# LCDTFT_CTRL_FT812.net
KiCad netlist of a schematic drawn in Altium Designer
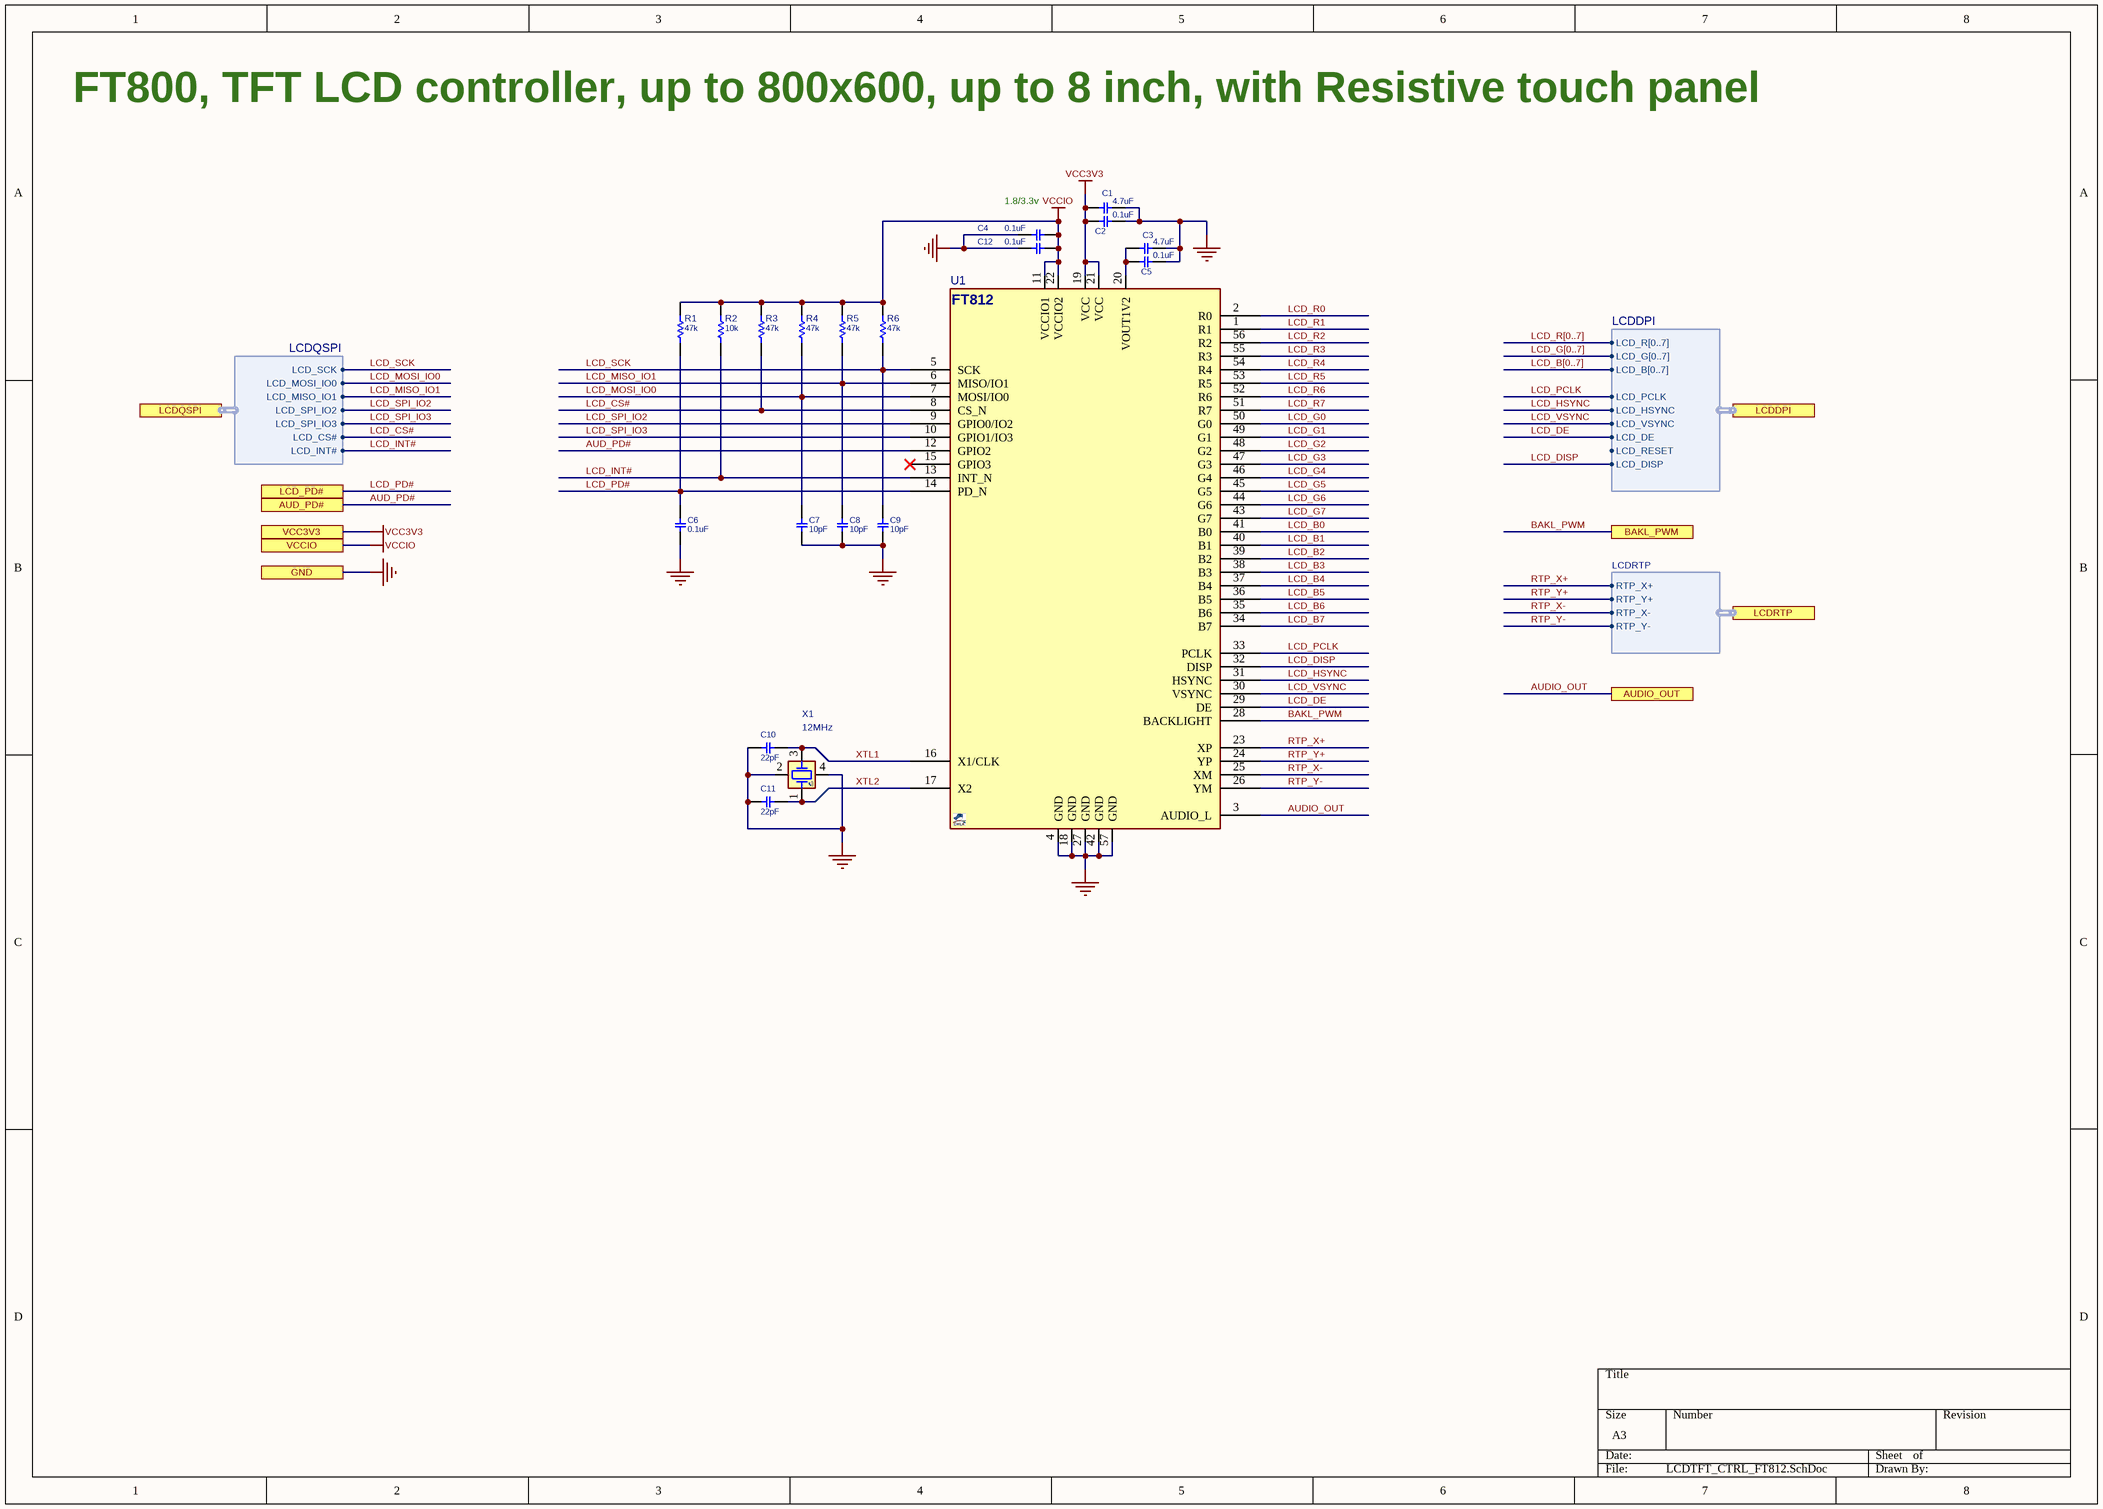
[diagram p0: LCDTFT_CTRL_FT812.SchDoc]

(export (version "E")
  (design (tool "Eeschema 10.0.6"))
  (components
    (comp (ref "C1")
      (value "4.7uF")
      (footprint "C0603")
      (description "CAP, MLCC")
      (libsource (lib "passive_smd") (part "CAP_SMD_MLCC"))
    )
    (comp (ref "C2")
      (value "0.1uF")
      (footprint "C0402")
      (description "CAP, MLCC")
      (fields (field (name "MANF_P#") "GRM155R71H104KE14D") (field (name "MANF") "Murata"))
      (libsource (lib "passive_smd") (part "CAP_SMD_MLCC"))
    )
    (comp (ref "C3")
      (value "4.7uF")
      (footprint "C0603")
      (description "CAP, MLCC")
      (libsource (lib "passive_smd") (part "CAP_SMD_MLCC"))
    )
    (comp (ref "C4")
      (value "0.1uF")
      (footprint "C0402")
      (description "CAP, MLCC")
      (fields (field (name "MANF_P#") "GRM155R71H104KE14D") (field (name "MANF") "Murata"))
      (libsource (lib "passive_smd") (part "CAP_SMD_MLCC"))
    )
    (comp (ref "C5")
      (value "0.1uF")
      (footprint "C0402")
      (description "CAP, MLCC")
      (fields (field (name "MANF_P#") "GRM155R71H104KE14D") (field (name "MANF") "Murata"))
      (libsource (lib "passive_smd") (part "CAP_SMD_MLCC"))
    )
    (comp (ref "C6")
      (value "0.1uF")
      (footprint "C0402")
      (description "CAP, MLCC")
      (fields (field (name "MANF_P#") "GRM155R71H104KE14D") (field (name "MANF") "Murata"))
      (libsource (lib "passive_smd") (part "CAP_SMD_MLCC"))
    )
    (comp (ref "C7")
      (value "10pF")
      (footprint "C0402")
      (description "CAP, MLCC")
      (libsource (lib "passive_smd") (part "CAP_SMD_MLCC"))
    )
    (comp (ref "C8")
      (value "10pF")
      (footprint "C0402")
      (description "CAP, MLCC")
      (libsource (lib "passive_smd") (part "CAP_SMD_MLCC"))
    )
    (comp (ref "C9")
      (value "10pF")
      (footprint "C0402")
      (description "CAP, MLCC")
      (libsource (lib "passive_smd") (part "CAP_SMD_MLCC"))
    )
    (comp (ref "C10")
      (value "22pF")
      (footprint "C0402")
      (description "CAP, MLCC")
      (libsource (lib "passive_smd") (part "CAP_SMD_MLCC"))
    )
    (comp (ref "C11")
      (value "22pF")
      (footprint "C0402")
      (description "CAP, MLCC")
      (libsource (lib "passive_smd") (part "CAP_SMD_MLCC"))
    )
    (comp (ref "C12")
      (value "0.1uF")
      (footprint "C0402")
      (description "CAP, MLCC")
      (fields (field (name "MANF_P#") "GRM155R71H104KE14D") (field (name "MANF") "Murata"))
      (libsource (lib "passive_smd") (part "CAP_SMD_MLCC"))
    )
    (comp (ref "R1")
      (value "47k")
      (footprint "R0402")
      (description "RESISTOR, SMD")
      (libsource (lib "passive_res_smd") (part "RES_SMD"))
    )
    (comp (ref "R2")
      (value "10k")
      (footprint "R0402")
      (description "RESISTOR, SMD")
      (libsource (lib "passive_res_smd") (part "RES_SMD"))
    )
    (comp (ref "R3")
      (value "47k")
      (footprint "R0402")
      (description "RESISTOR, SMD")
      (libsource (lib "passive_res_smd") (part "RES_SMD"))
    )
    (comp (ref "R4")
      (value "47k")
      (footprint "R0402")
      (description "RESISTOR, SMD")
      (libsource (lib "passive_res_smd") (part "RES_SMD"))
    )
    (comp (ref "R5")
      (value "47k")
      (footprint "R0402")
      (description "RESISTOR, SMD")
      (libsource (lib "passive_res_smd") (part "RES_SMD"))
    )
    (comp (ref "R6")
      (value "47k")
      (footprint "R0402")
      (description "RESISTOR, SMD")
      (libsource (lib "passive_res_smd") (part "RES_SMD"))
    )
    (comp (ref "U1")
      (value "FT812")
      (footprint "QFN50_56T")
      (description "LCD Display Controller, Embedded Video Engine, QFN-56")
      (fields (field (name "MANF") "FTDI/Bridgetek") (field (name "MANF_P#") "FT812Q"))
      (libsource (lib "lcdtft_controller") (part "FT812_QFN56"))
    )
    (comp (ref "X1")
      (value "12MHz")
      (footprint "XTL_4_3225")
      (description "Crystal 12MHz")
      (fields (field (name "MANF") "ECS") (field (name "MANF_P#") "ECS-120-18-33-JEM-TR"))
      (libsource (lib "crystal") (part "XTL_4_12MHz_3225"))
    )
  )
  (nets
    (net (code "4") (name "/AUDIO_OUT") (class "Default")
      (node (ref "U1") (pin "3") (pinfunction "AUDIO_L_3") (pintype "passive"))
    )
    (net (code "5") (name "/AUD_PD#") (class "Default")
      (node (ref "U1") (pin "12") (pinfunction "GPIO2_12") (pintype "passive"))
    )
    (net (code "6") (name "/BAKL_PWM") (class "Default")
      (node (ref "U1") (pin "28") (pinfunction "BACKLIGHT_28") (pintype "passive"))
    )
    (net (code "8") (name "/LCD_B0") (class "Default")
      (node (ref "U1") (pin "41") (pinfunction "B0_41") (pintype "passive"))
    )
    (net (code "9") (name "/LCD_B1") (class "Default")
      (node (ref "U1") (pin "40") (pinfunction "B1_40") (pintype "passive"))
    )
    (net (code "10") (name "/LCD_B2") (class "Default")
      (node (ref "U1") (pin "39") (pinfunction "B2_39") (pintype "passive"))
    )
    (net (code "11") (name "/LCD_B3") (class "Default")
      (node (ref "U1") (pin "38") (pinfunction "B3_38") (pintype "passive"))
    )
    (net (code "12") (name "/LCD_B4") (class "Default")
      (node (ref "U1") (pin "37") (pinfunction "B4_37") (pintype "passive"))
    )
    (net (code "13") (name "/LCD_B5") (class "Default")
      (node (ref "U1") (pin "36") (pinfunction "B5_36") (pintype "passive"))
    )
    (net (code "14") (name "/LCD_B6") (class "Default")
      (node (ref "U1") (pin "35") (pinfunction "B6_35") (pintype "passive"))
    )
    (net (code "15") (name "/LCD_B7") (class "Default")
      (node (ref "U1") (pin "34") (pinfunction "B7_34") (pintype "passive"))
    )
    (net (code "16") (name "/LCD_CS#") (class "Default")
      (node (ref "R3") (pin "2") (pinfunction "2_2") (pintype "passive"))
      (node (ref "U1") (pin "8") (pinfunction "CS_N_8") (pintype "passive"))
    )
    (net (code "17") (name "/LCD_DE") (class "Default")
      (node (ref "U1") (pin "29") (pinfunction "DE_29") (pintype "passive"))
    )
    (net (code "18") (name "/LCD_DISP") (class "Default")
      (node (ref "U1") (pin "32") (pinfunction "DISP_32") (pintype "passive"))
    )
    (net (code "19") (name "/LCD_G0") (class "Default")
      (node (ref "U1") (pin "50") (pinfunction "G0_50") (pintype "passive"))
    )
    (net (code "20") (name "/LCD_G1") (class "Default")
      (node (ref "U1") (pin "49") (pinfunction "G1_49") (pintype "passive"))
    )
    (net (code "21") (name "/LCD_G2") (class "Default")
      (node (ref "U1") (pin "48") (pinfunction "G2_48") (pintype "passive"))
    )
    (net (code "22") (name "/LCD_G3") (class "Default")
      (node (ref "U1") (pin "47") (pinfunction "G3_47") (pintype "passive"))
    )
    (net (code "23") (name "/LCD_G4") (class "Default")
      (node (ref "U1") (pin "46") (pinfunction "G4_46") (pintype "passive"))
    )
    (net (code "24") (name "/LCD_G5") (class "Default")
      (node (ref "U1") (pin "45") (pinfunction "G5_45") (pintype "passive"))
    )
    (net (code "25") (name "/LCD_G6") (class "Default")
      (node (ref "U1") (pin "44") (pinfunction "G6_44") (pintype "passive"))
    )
    (net (code "26") (name "/LCD_G7") (class "Default")
      (node (ref "U1") (pin "43") (pinfunction "G7_43") (pintype "passive"))
    )
    (net (code "28") (name "/LCD_HSYNC") (class "Default")
      (node (ref "U1") (pin "31") (pinfunction "HSYNC_31") (pintype "passive"))
    )
    (net (code "29") (name "/LCD_INT#") (class "Default")
      (node (ref "R2") (pin "2") (pinfunction "2_2") (pintype "passive"))
      (node (ref "U1") (pin "13") (pinfunction "INT_N_13") (pintype "passive"))
    )
    (net (code "30") (name "/LCD_MISO_IO1") (class "Default")
      (node (ref "C8") (pin "1") (pinfunction "1_1") (pintype "passive"))
      (node (ref "R5") (pin "2") (pinfunction "2_2") (pintype "passive"))
      (node (ref "U1") (pin "6") (pinfunction "MISO/IO1_6") (pintype "passive"))
    )
    (net (code "31") (name "/LCD_MOSI_IO0") (class "Default")
      (node (ref "C7") (pin "1") (pinfunction "1_1") (pintype "passive"))
      (node (ref "R4") (pin "2") (pinfunction "2_2") (pintype "passive"))
      (node (ref "U1") (pin "7") (pinfunction "MOSI/IO0_7") (pintype "passive"))
    )
    (net (code "32") (name "/LCD_PCLK") (class "Default")
      (node (ref "U1") (pin "33") (pinfunction "PCLK_33") (pintype "passive"))
    )
    (net (code "33") (name "/LCD_PD#") (class "Default")
      (node (ref "C6") (pin "1") (pinfunction "1_1") (pintype "passive"))
      (node (ref "R1") (pin "2") (pinfunction "2_2") (pintype "passive"))
      (node (ref "U1") (pin "14") (pinfunction "PD_N_14") (pintype "passive"))
    )
    (net (code "34") (name "/LCD_R0") (class "Default")
      (node (ref "U1") (pin "2") (pinfunction "R0_2") (pintype "passive"))
    )
    (net (code "35") (name "/LCD_R1") (class "Default")
      (node (ref "U1") (pin "1") (pinfunction "R1_1") (pintype "passive"))
    )
    (net (code "36") (name "/LCD_R2") (class "Default")
      (node (ref "U1") (pin "56") (pinfunction "R2_56") (pintype "passive"))
    )
    (net (code "37") (name "/LCD_R3") (class "Default")
      (node (ref "U1") (pin "55") (pinfunction "R3_55") (pintype "passive"))
    )
    (net (code "38") (name "/LCD_R4") (class "Default")
      (node (ref "U1") (pin "54") (pinfunction "R4_54") (pintype "passive"))
    )
    (net (code "39") (name "/LCD_R5") (class "Default")
      (node (ref "U1") (pin "53") (pinfunction "R5_53") (pintype "passive"))
    )
    (net (code "40") (name "/LCD_R6") (class "Default")
      (node (ref "U1") (pin "52") (pinfunction "R6_52") (pintype "passive"))
    )
    (net (code "41") (name "/LCD_R7") (class "Default")
      (node (ref "U1") (pin "51") (pinfunction "R7_51") (pintype "passive"))
    )
    (net (code "43") (name "/LCD_SCK") (class "Default")
      (node (ref "C9") (pin "1") (pinfunction "1_1") (pintype "passive"))
      (node (ref "R6") (pin "2") (pinfunction "2_2") (pintype "passive"))
      (node (ref "U1") (pin "5") (pinfunction "SCK_5") (pintype "passive"))
    )
    (net (code "44") (name "/LCD_SPI_IO2") (class "Default")
      (node (ref "U1") (pin "9") (pinfunction "GPIO0/IO2_9") (pintype "passive"))
    )
    (net (code "45") (name "/LCD_SPI_IO3") (class "Default")
      (node (ref "U1") (pin "10") (pinfunction "GPIO1/IO3_10") (pintype "passive"))
    )
    (net (code "46") (name "/LCD_VSYNC") (class "Default")
      (node (ref "U1") (pin "30") (pinfunction "VSYNC_30") (pintype "passive"))
    )
    (net (code "47") (name "/RTP_X+") (class "Default")
      (node (ref "U1") (pin "23") (pinfunction "XP_23") (pintype "passive"))
    )
    (net (code "48") (name "/RTP_X-") (class "Default")
      (node (ref "U1") (pin "25") (pinfunction "XM_25") (pintype "passive"))
    )
    (net (code "49") (name "/RTP_Y+") (class "Default")
      (node (ref "U1") (pin "24") (pinfunction "YP_24") (pintype "passive"))
    )
    (net (code "50") (name "/RTP_Y-") (class "Default")
      (node (ref "U1") (pin "26") (pinfunction "YM_26") (pintype "passive"))
    )
    (net (code "51") (name "/XTL1") (class "Default")
      (node (ref "C10") (pin "2") (pinfunction "2_2") (pintype "passive"))
      (node (ref "U1") (pin "16") (pinfunction "X1/CLK_16") (pintype "passive"))
      (node (ref "X1") (pin "3") (pinfunction "2_3") (pintype "passive"))
    )
    (net (code "52") (name "/XTL2") (class "Default")
      (node (ref "C11") (pin "1") (pinfunction "1_1") (pintype "passive"))
      (node (ref "U1") (pin "17") (pinfunction "X2_17") (pintype "passive"))
      (node (ref "X1") (pin "1") (pinfunction "1_1") (pintype "passive"))
    )
    (net (code "56") (name "GND") (class "Default")
      (node (ref "C1") (pin "1") (pinfunction "1_1") (pintype "passive"))
      (node (ref "C10") (pin "1") (pinfunction "1_1") (pintype "passive"))
      (node (ref "C11") (pin "2") (pinfunction "2_2") (pintype "passive"))
      (node (ref "C12") (pin "2") (pinfunction "2_2") (pintype "passive"))
      (node (ref "C2") (pin "1") (pinfunction "1_1") (pintype "passive"))
      (node (ref "C3") (pin "1") (pinfunction "1_1") (pintype "passive"))
      (node (ref "C4") (pin "2") (pinfunction "2_2") (pintype "passive"))
      (node (ref "C5") (pin "1") (pinfunction "1_1") (pintype "passive"))
      (node (ref "C6") (pin "2") (pinfunction "2_2") (pintype "passive"))
      (node (ref "C7") (pin "2") (pinfunction "2_2") (pintype "passive"))
      (node (ref "C8") (pin "2") (pinfunction "2_2") (pintype "passive"))
      (node (ref "C9") (pin "2") (pinfunction "2_2") (pintype "passive"))
      (node (ref "U1") (pin "18") (pinfunction "GND_18") (pintype "passive"))
      (node (ref "U1") (pin "27") (pinfunction "GND_27") (pintype "passive"))
      (node (ref "U1") (pin "4") (pinfunction "GND_4") (pintype "passive"))
      (node (ref "U1") (pin "42") (pinfunction "GND_42") (pintype "passive"))
      (node (ref "U1") (pin "57") (pinfunction "GND_57") (pintype "passive"))
      (node (ref "X1") (pin "2") (pinfunction "2_2") (pintype "passive"))
      (node (ref "X1") (pin "4") (pinfunction "4_4") (pintype "passive"))
    )
    (net (code "57") (name "Net-(U1-VOUT1V2)") (class "Default")
      (node (ref "C3") (pin "2") (pinfunction "2_2") (pintype "passive"))
      (node (ref "C5") (pin "2") (pinfunction "2_2") (pintype "passive"))
      (node (ref "U1") (pin "20") (pinfunction "VOUT1V2_20") (pintype "passive"))
    )
    (net (code "58") (name "VCC3V3") (class "Default")
      (node (ref "C1") (pin "2") (pinfunction "2_2") (pintype "passive"))
      (node (ref "C2") (pin "2") (pinfunction "2_2") (pintype "passive"))
      (node (ref "U1") (pin "19") (pinfunction "VCC_19") (pintype "passive"))
      (node (ref "U1") (pin "21") (pinfunction "VCC_21") (pintype "passive"))
    )
    (net (code "59") (name "VCCIO") (class "Default")
      (node (ref "C12") (pin "1") (pinfunction "1_1") (pintype "passive"))
      (node (ref "C4") (pin "1") (pinfunction "1_1") (pintype "passive"))
      (node (ref "R1") (pin "1") (pinfunction "1_1") (pintype "passive"))
      (node (ref "R2") (pin "1") (pinfunction "1_1") (pintype "passive"))
      (node (ref "R3") (pin "1") (pinfunction "1_1") (pintype "passive"))
      (node (ref "R4") (pin "1") (pinfunction "1_1") (pintype "passive"))
      (node (ref "R5") (pin "1") (pinfunction "1_1") (pintype "passive"))
      (node (ref "R6") (pin "1") (pinfunction "1_1") (pintype "passive"))
      (node (ref "U1") (pin "11") (pinfunction "VCCIO1_11") (pintype "passive"))
      (node (ref "U1") (pin "22") (pinfunction "VCCIO2_22") (pintype "passive"))
    )
    (net (code "60") (name "unconnected-(U1-GPIO3-Pad15)") (class "Default")
      (node (ref "U1") (pin "15") (pinfunction "GPIO3_15") (pintype "passive+no_connect"))
    )
  )
)
